# SDC-rev2.net
KiCad netlist of a schematic drawn in Altium Designer
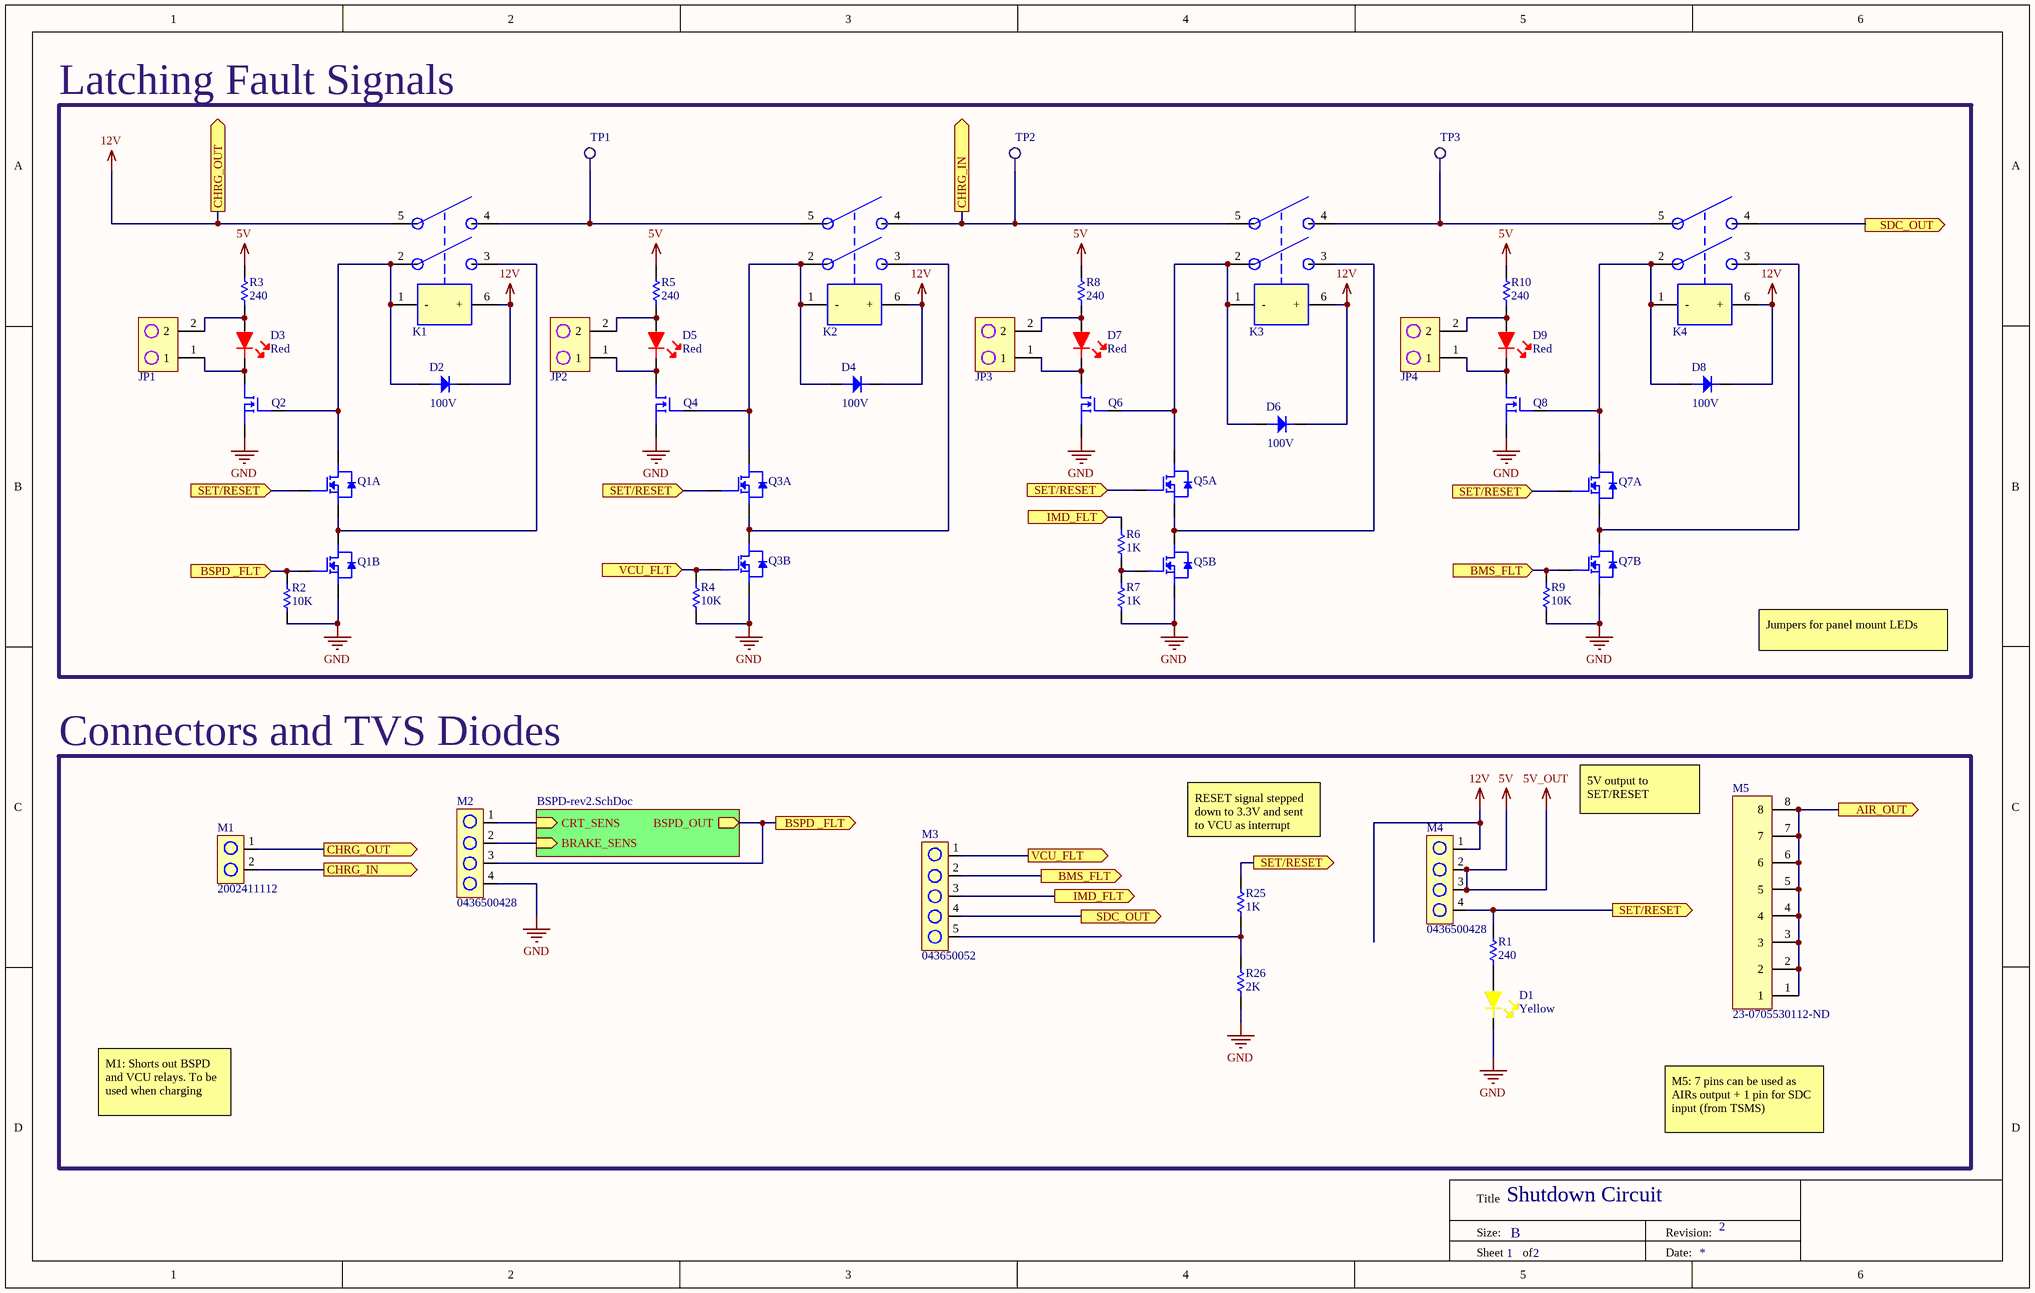
[diagram p0: SDC-rev2.SchDoc]

(export (version "E")
  (design (tool "Eeschema 10.0.6"))
  (components
    (comp (ref "D1")
      (value "Yellow")
      (footprint "LED-0603")
      (description "LED YELLOW CLEAR 0603 SMD")
      (fields
        (field (name "MANUFACTURER") "Wurth Electronics")
        (field (name "MANUFACTURER PART NUMBER") "150060YS75000")
      )
      (libsource (lib "LEDs") (part "LED-Yellow"))
    )
    (comp (ref "D2")
      (value "100V")
      (footprint "DO-214AA")
      (description "DIODE GEN PURP 600V 5A SMB")
      (fields (field (name "MANUFACTURER") "MCC") (field (name "MANUFACTURER PART NUMBER") "SK510B-LTP"))
      (libsource (lib "Diodes") (part "Diode-600V-5A"))
    )
    (comp (ref "D3")
      (value "Red")
      (footprint "LED-0603")
      (description "LED RED CLEAR 0603 SMD")
      (fields (field (name "MANUFACTURER") "Inolux") (field (name "MANUFACTURER PART NUMBER") "IN-S63ATR"))
      (libsource (lib "LEDs") (part "LED-Red-Bright"))
    )
    (comp (ref "D4")
      (value "100V")
      (footprint "DO-214AA")
      (description "DIODE GEN PURP 600V 5A SMB")
      (fields (field (name "MANUFACTURER") "MCC") (field (name "MANUFACTURER PART NUMBER") "SK510B-LTP"))
      (libsource (lib "Diodes") (part "Diode-600V-5A"))
    )
    (comp (ref "D5")
      (value "Red")
      (footprint "LED-0603")
      (description "LED RED CLEAR 0603 SMD")
      (fields (field (name "MANUFACTURER") "Inolux") (field (name "MANUFACTURER PART NUMBER") "IN-S63ATR"))
      (libsource (lib "LEDs") (part "LED-Red-Bright"))
    )
    (comp (ref "D6")
      (value "100V")
      (footprint "DO-214AA")
      (description "DIODE GEN PURP 600V 5A SMB")
      (fields (field (name "MANUFACTURER") "MCC") (field (name "MANUFACTURER PART NUMBER") "SK510B-LTP"))
      (libsource (lib "Diodes") (part "Diode-600V-5A"))
    )
    (comp (ref "D7")
      (value "Red")
      (footprint "LED-0603")
      (description "LED RED CLEAR 0603 SMD")
      (fields (field (name "MANUFACTURER") "Inolux") (field (name "MANUFACTURER PART NUMBER") "IN-S63ATR"))
      (libsource (lib "LEDs") (part "LED-Red-Bright"))
    )
    (comp (ref "D8")
      (value "100V")
      (footprint "DO-214AA")
      (description "DIODE GEN PURP 600V 5A SMB")
      (fields (field (name "MANUFACTURER") "MCC") (field (name "MANUFACTURER PART NUMBER") "SK510B-LTP"))
      (libsource (lib "Diodes") (part "Diode-600V-5A"))
    )
    (comp (ref "D9")
      (value "Red")
      (footprint "LED-0603")
      (description "LED RED CLEAR 0603 SMD")
      (fields (field (name "MANUFACTURER") "Inolux") (field (name "MANUFACTURER PART NUMBER") "IN-S63ATR"))
      (libsource (lib "LEDs") (part "LED-Red-Bright"))
    )
    (comp (ref "JP1")
      (value "732-5315-ND")
      (footprint "2PIN-JP")
      (description "CONN HEADER VERT 2POS 2.54MM")
      (libsource (lib "Connectors") (part "2PIN-TEST"))
    )
    (comp (ref "JP2")
      (value "732-5315-ND")
      (footprint "2PIN-JP")
      (description "CONN HEADER VERT 2POS 2.54MM")
      (libsource (lib "Connectors") (part "2PIN-TEST"))
    )
    (comp (ref "JP3")
      (value "732-5315-ND")
      (footprint "2PIN-JP")
      (description "CONN HEADER VERT 2POS 2.54MM")
      (libsource (lib "Connectors") (part "2PIN-TEST"))
    )
    (comp (ref "JP4")
      (value "732-5315-ND")
      (footprint "2PIN-JP")
      (description "CONN HEADER VERT 2POS 2.54MM")
      (libsource (lib "Connectors") (part "2PIN-TEST"))
    )
    (comp (ref "K1")
      (value "5-1419124-6")
      (footprint "RELAY DPST SDC")
      (description "General Purpose Relay, Osa Series, Power, Non Latching, Dpst-No, 12 Vdc, 3 A Rohs Compliant: Yes")
      (fields (field (name "MANUFACTURER") "TE Connectivity"))
      (libsource (lib "SDC") (part "5-1419124-6"))
    )
    (comp (ref "K2")
      (value "5-1419124-6")
      (footprint "RELAY DPST SDC")
      (description "General Purpose Relay, Osa Series, Power, Non Latching, Dpst-No, 12 Vdc, 3 A Rohs Compliant: Yes")
      (fields (field (name "MANUFACTURER") "TE Connectivity"))
      (libsource (lib "SDC") (part "5-1419124-6"))
    )
    (comp (ref "K3")
      (value "5-1419124-6")
      (footprint "RELAY DPST SDC")
      (description "General Purpose Relay, Osa Series, Power, Non Latching, Dpst-No, 12 Vdc, 3 A Rohs Compliant: Yes")
      (fields (field (name "MANUFACTURER") "TE Connectivity"))
      (libsource (lib "SDC") (part "5-1419124-6"))
    )
    (comp (ref "K4")
      (value "5-1419124-6")
      (footprint "RELAY DPST SDC")
      (description "General Purpose Relay, Osa Series, Power, Non Latching, Dpst-No, 12 Vdc, 3 A Rohs Compliant: Yes")
      (fields (field (name "MANUFACTURER") "TE Connectivity"))
      (libsource (lib "SDC") (part "5-1419124-6"))
    )
    (comp (ref "M1")
      (value "2002411112")
      (footprint "2-PIN MOLEX")
      (description "CONN HEADER VERT 2POS 5.7MM, 12-16AWG")
      (libsource (lib "SDC") (part "2002411112"))
    )
    (comp (ref "M2")
      (value "0436500428")
      (footprint "4-PIN MOLEX")
      (description "4 PIN HDR, 3MM PITCH, 18-30 AWG")
      (fields (field (name "MANUFACTURER") "Molex"))
      (libsource (lib "SDC") (part "0436500428"))
    )
    (comp (ref "M3")
      (value "043650052")
      (footprint "5-PIN MOLEX")
      (description "CONN HEADER VERT 5POS 3MM")
      (libsource (lib "SDC") (part "0436500528"))
    )
    (comp (ref "M4")
      (value "0436500428")
      (footprint "4-PIN MOLEX")
      (description "4 PIN HDR, 3MM PITCH, 18-30 AWG")
      (fields (field (name "MANUFACTURER") "Molex"))
      (libsource (lib "SDC") (part "0436500428"))
    )
    (comp (ref "M5")
      (value "23-0705530112-ND")
      (footprint "8PIN")
      (description "CONN HEADER R/A 8POS 2.54MM")
      (fields (field (name "MANUFACTURER") "Molex") (field (name "MANUFACTURER PART NUMBER") "70553-0112"))
      (libsource (lib "Connectors") (part "8PIN"))
    )
    (comp (ref "Q1")
      (value "DMN63D1LDW")
      (footprint "DMN63D1LDW")
      (description "MOSFET 2N-CH 60V 0.25A SOT363")
      (fields
        (field (name "MANUFACTURER") "Toshiba")
        (field (name "MANUFACTURER PART NUMBER") "SSM6N7002CFU,LF")
      )
      (libsource (lib "SDC") (part "DMN63D1LDW"))
    )
    (comp (ref "Q2")
      (value "DMN6140L-13DICT-ND")
      (footprint "SOT-23-3")
      (description "MOSFET N-CH 60V 1.6A SOT23")
      (fields (field (name "MANUFACTURER") "Diodes") (field (name "MANUFACTURER PART NUMBER") "DMN6140L-13"))
      (libsource (lib "Transistors") (part "N-FET-60V-1.6A"))
    )
    (comp (ref "Q3")
      (value "DMN63D1LDW")
      (footprint "DMN63D1LDW")
      (description "MOSFET 2N-CH 60V 0.25A SOT363")
      (fields
        (field (name "MANUFACTURER") "Toshiba")
        (field (name "MANUFACTURER PART NUMBER") "SSM6N7002CFU,LF")
      )
      (libsource (lib "SDC") (part "DMN63D1LDW"))
    )
    (comp (ref "Q4")
      (value "DMN6140L-13DICT-ND")
      (footprint "SOT-23-3")
      (description "MOSFET N-CH 60V 1.6A SOT23")
      (fields (field (name "MANUFACTURER") "Diodes") (field (name "MANUFACTURER PART NUMBER") "DMN6140L-13"))
      (libsource (lib "Transistors") (part "N-FET-60V-1.6A"))
    )
    (comp (ref "Q5")
      (value "DMN63D1LDW")
      (footprint "DMN63D1LDW")
      (description "MOSFET 2N-CH 60V 0.25A SOT363")
      (fields
        (field (name "MANUFACTURER") "Toshiba")
        (field (name "MANUFACTURER PART NUMBER") "SSM6N7002CFU,LF")
      )
      (libsource (lib "SDC") (part "DMN63D1LDW"))
    )
    (comp (ref "Q6")
      (value "DMN6140L-13DICT-ND")
      (footprint "SOT-23-3")
      (description "MOSFET N-CH 60V 1.6A SOT23")
      (fields (field (name "MANUFACTURER") "Diodes") (field (name "MANUFACTURER PART NUMBER") "DMN6140L-13"))
      (libsource (lib "Transistors") (part "N-FET-60V-1.6A"))
    )
    (comp (ref "Q7")
      (value "DMN63D1LDW")
      (footprint "DMN63D1LDW")
      (description "MOSFET 2N-CH 60V 0.25A SOT363")
      (fields
        (field (name "MANUFACTURER") "Toshiba")
        (field (name "MANUFACTURER PART NUMBER") "SSM6N7002CFU,LF")
      )
      (libsource (lib "SDC") (part "DMN63D1LDW"))
    )
    (comp (ref "Q8")
      (value "DMN6140L-13DICT-ND")
      (footprint "SOT-23-3")
      (description "MOSFET N-CH 60V 1.6A SOT23")
      (fields (field (name "MANUFACTURER") "Diodes") (field (name "MANUFACTURER PART NUMBER") "DMN6140L-13"))
      (libsource (lib "Transistors") (part "N-FET-60V-1.6A"))
    )
    (comp (ref "R1")
      (value "240")
      (footprint "RES-0603")
      (description "RES SMD 240 OHM 5% 1/4W 0603")
      (fields
        (field (name "MANUFACTURER") "Vishay")
        (field (name "MANUFACTURER PART NUMBER") "CRCW0603220RJNEA")
      )
      (libsource (lib "SDC") (part "ESR03EZPJ241"))
    )
    (comp (ref "R2")
      (value "10K")
      (footprint "RES-0603")
      (description "RES SMD 10K OHM 1% 1/10W 0603")
      (fields
        (field (name "MANUFACTURER") "Vishay")
        (field (name "MANUFACTURER PART NUMBER") "CRCW060310K0FKEA")
      )
      (libsource (lib "SDC") (part "CRCW060310K0FKEA"))
    )
    (comp (ref "R3")
      (value "240")
      (footprint "RES-0603")
      (description "RES SMD 240 OHM 5% 1/4W 0603")
      (fields
        (field (name "MANUFACTURER") "Vishay")
        (field (name "MANUFACTURER PART NUMBER") "CRCW0603220RJNEA")
      )
      (libsource (lib "SDC") (part "ESR03EZPJ241"))
    )
    (comp (ref "R4")
      (value "10K")
      (footprint "RES-0603")
      (description "RES SMD 10K OHM 1% 1/10W 0603")
      (fields
        (field (name "MANUFACTURER") "Vishay")
        (field (name "MANUFACTURER PART NUMBER") "CRCW060310K0FKEA")
      )
      (libsource (lib "SDC") (part "CRCW060310K0FKEA"))
    )
    (comp (ref "R5")
      (value "240")
      (footprint "RES-0603")
      (description "RES SMD 240 OHM 5% 1/4W 0603")
      (fields
        (field (name "MANUFACTURER") "Vishay")
        (field (name "MANUFACTURER PART NUMBER") "CRCW0603220RJNEA")
      )
      (libsource (lib "SDC") (part "ESR03EZPJ241"))
    )
    (comp (ref "R6")
      (value "1K")
      (footprint "RES-0603")
      (description "RES SMD 1K OHM 1% 1/10W 0603")
      (fields
        (field (name "MANUFACTURER") "Vishay Dale")
        (field (name "MANUFACTURER PART NUMBER") "CRCW06031K00FKEA")
      )
      (libsource (lib "SDC") (part "CRCW06031K00FKEA"))
    )
    (comp (ref "R7")
      (value "1K")
      (footprint "RES-0603")
      (description "RES SMD 1K OHM 1% 1/10W 0603")
      (fields
        (field (name "MANUFACTURER") "Vishay Dale")
        (field (name "MANUFACTURER PART NUMBER") "CRCW06031K00FKEA")
      )
      (libsource (lib "SDC") (part "CRCW06031K00FKEA"))
    )
    (comp (ref "R8")
      (value "240")
      (footprint "RES-0603")
      (description "RES SMD 240 OHM 5% 1/4W 0603")
      (fields
        (field (name "MANUFACTURER") "Vishay")
        (field (name "MANUFACTURER PART NUMBER") "CRCW0603220RJNEA")
      )
      (libsource (lib "SDC") (part "ESR03EZPJ241"))
    )
    (comp (ref "R9")
      (value "10K")
      (footprint "RES-0603")
      (description "RES SMD 10K OHM 1% 1/10W 0603")
      (fields
        (field (name "MANUFACTURER") "Vishay")
        (field (name "MANUFACTURER PART NUMBER") "CRCW060310K0FKEA")
      )
      (libsource (lib "SDC") (part "CRCW060310K0FKEA"))
    )
    (comp (ref "R10")
      (value "240")
      (footprint "RES-0603")
      (description "RES SMD 240 OHM 5% 1/4W 0603")
      (fields
        (field (name "MANUFACTURER") "Vishay")
        (field (name "MANUFACTURER PART NUMBER") "CRCW0603220RJNEA")
      )
      (libsource (lib "SDC") (part "ESR03EZPJ241"))
    )
    (comp (ref "R25")
      (value "1K")
      (footprint "RES-0603")
      (description "RES SMD 240 OHM 5% 1/4W 0603")
      (fields
        (field (name "MANUFACTURER") "Vishay")
        (field (name "MANUFACTURER PART NUMBER") "CRCW0603220RJNEA")
      )
      (libsource (lib "SDC") (part "ESR03EZPJ241"))
    )
    (comp (ref "R26")
      (value "2K")
      (footprint "RES-0603")
      (description "RES SMD 2K OHM 0.1% 1/10W 0603")
      (fields
        (field (name "MANUFACTURER") "Vishay Dale")
        (field (name "MANUFACTURER PART NUMBER") "CRCW06031K00FKEA")
      )
      (libsource (lib "SDC") (part "ERA-3AEB202V"))
    )
    (comp (ref "TP1")
      (value "Testpoint2")
      (footprint "TP2")
      (description "Single layer pad TP")
      (libsource (lib "Misc") (part "Testpoint2"))
    )
    (comp (ref "TP2")
      (value "Testpoint2")
      (footprint "TP2")
      (description "Single layer pad TP")
      (libsource (lib "Misc") (part "Testpoint2"))
    )
    (comp (ref "TP3")
      (value "Testpoint2")
      (footprint "TP2")
      (description "Single layer pad TP")
      (libsource (lib "Misc") (part "Testpoint2"))
    )
  )
  (nets
    (net (code "1") (name "/AIR_OUT") (class "Default")
      (node (ref "M5") (pin "1") (pinfunction "1_1") (pintype "passive"))
      (node (ref "M5") (pin "2") (pinfunction "2_2") (pintype "passive"))
      (node (ref "M5") (pin "3") (pinfunction "3_3") (pintype "passive"))
      (node (ref "M5") (pin "4") (pinfunction "4_4") (pintype "passive"))
      (node (ref "M5") (pin "5") (pinfunction "5_5") (pintype "passive"))
      (node (ref "M5") (pin "6") (pinfunction "6_6") (pintype "passive"))
      (node (ref "M5") (pin "7") (pinfunction "7_7") (pintype "passive"))
      (node (ref "M5") (pin "8") (pinfunction "8_8") (pintype "passive"))
    )
    (net (code "2") (name "/BMS_FLT") (class "Default")
      (node (ref "M3") (pin "2") (pinfunction "2_2") (pintype "passive"))
      (node (ref "Q7") (pin "5") (pinfunction "G2_5") (pintype "passive"))
      (node (ref "R9") (pin "1") (pinfunction "1_1") (pintype "passive"))
    )
    (net (code "3") (name "/BRAKE_SENS") (class "Default")
      (node (ref "M2") (pin "2") (pinfunction "2_2") (pintype "passive"))
    )
    (net (code "4") (name "/BSPD _FLT") (class "Default")
      (node (ref "M2") (pin "3") (pinfunction "3_3") (pintype "passive"))
      (node (ref "Q1") (pin "5") (pinfunction "G2_5") (pintype "passive"))
      (node (ref "R2") (pin "1") (pinfunction "1_1") (pintype "passive"))
    )
    (net (code "5") (name "/CHRG_IN") (class "Default")
      (node (ref "K2") (pin "4") (pintype "passive"))
      (node (ref "K3") (pin "5") (pintype "passive"))
      (node (ref "M1") (pin "2") (pinfunction "2_2") (pintype "passive"))
      (node (ref "TP2") (pin "1") (pinfunction "1_1") (pintype "passive"))
    )
    (net (code "6") (name "/CRT_SENS") (class "Default")
      (node (ref "M2") (pin "1") (pinfunction "1_1") (pintype "passive"))
    )
    (net (code "7") (name "/IMD_FLT") (class "Default")
      (node (ref "M3") (pin "3") (pinfunction "3_3") (pintype "passive"))
      (node (ref "R6") (pin "1") (pinfunction "1_1") (pintype "passive"))
    )
    (net (code "8") (name "/SDC_OUT") (class "Default")
      (node (ref "K4") (pin "4") (pintype "passive"))
      (node (ref "M3") (pin "4") (pinfunction "4_4") (pintype "passive"))
    )
    (net (code "9") (name "/SET{slash}RESET") (class "Default")
      (node (ref "M4") (pin "4") (pinfunction "4_4") (pintype "passive"))
      (node (ref "Q1") (pin "2") (pinfunction "G1_2") (pintype "passive"))
      (node (ref "Q3") (pin "2") (pinfunction "G1_2") (pintype "passive"))
      (node (ref "Q5") (pin "2") (pinfunction "G1_2") (pintype "passive"))
      (node (ref "Q7") (pin "2") (pinfunction "G1_2") (pintype "passive"))
      (node (ref "R1") (pin "2") (pinfunction "2_2") (pintype "passive"))
      (node (ref "R25") (pin "2") (pinfunction "2_2") (pintype "passive"))
    )
    (net (code "10") (name "/VCU_FLT") (class "Default")
      (node (ref "M3") (pin "1") (pinfunction "1_1") (pintype "passive"))
      (node (ref "Q3") (pin "5") (pinfunction "G2_5") (pintype "passive"))
      (node (ref "R4") (pin "1") (pinfunction "1_1") (pintype "passive"))
    )
    (net (code "11") (name "5V") (class "Default")
      (node (ref "M4") (pin "2") (pinfunction "2_2") (pintype "passive"))
      (node (ref "M4") (pin "3") (pinfunction "3_3") (pintype "passive"))
      (node (ref "R10") (pin "2") (pinfunction "2_2") (pintype "passive"))
      (node (ref "R3") (pin "2") (pinfunction "2_2") (pintype "passive"))
      (node (ref "R5") (pin "2") (pinfunction "2_2") (pintype "passive"))
      (node (ref "R8") (pin "2") (pinfunction "2_2") (pintype "passive"))
    )
    (net (code "12") (name "12V") (class "Default")
      (node (ref "D2") (pin "1") (pinfunction "1_1") (pintype "passive"))
      (node (ref "D4") (pin "1") (pinfunction "1_1") (pintype "passive"))
      (node (ref "D6") (pin "1") (pinfunction "1_1") (pintype "passive"))
      (node (ref "D8") (pin "1") (pinfunction "1_1") (pintype "passive"))
      (node (ref "K1") (pin "5") (pintype "passive"))
      (node (ref "K1") (pin "6") (pinfunction "+_6") (pintype "passive"))
      (node (ref "K2") (pin "6") (pinfunction "+_6") (pintype "passive"))
      (node (ref "K3") (pin "6") (pinfunction "+_6") (pintype "passive"))
      (node (ref "K4") (pin "6") (pinfunction "+_6") (pintype "passive"))
      (node (ref "M1") (pin "1") (pinfunction "1_1") (pintype "passive"))
      (node (ref "M4") (pin "1") (pinfunction "1_1") (pintype "passive"))
    )
    (net (code "13") (name "GND") (class "Default")
      (node (ref "D1") (pin "2") (pinfunction "2_2") (pintype "passive"))
      (node (ref "M2") (pin "4") (pinfunction "4_4") (pintype "passive"))
      (node (ref "Q1") (pin "4") (pinfunction "S2_4") (pintype "passive"))
      (node (ref "Q2") (pin "3") (pinfunction "3_3") (pintype "passive"))
      (node (ref "Q3") (pin "4") (pinfunction "S2_4") (pintype "passive"))
      (node (ref "Q4") (pin "3") (pinfunction "3_3") (pintype "passive"))
      (node (ref "Q5") (pin "4") (pinfunction "S2_4") (pintype "passive"))
      (node (ref "Q6") (pin "3") (pinfunction "3_3") (pintype "passive"))
      (node (ref "Q7") (pin "4") (pinfunction "S2_4") (pintype "passive"))
      (node (ref "Q8") (pin "3") (pinfunction "3_3") (pintype "passive"))
      (node (ref "R2") (pin "2") (pinfunction "2_2") (pintype "passive"))
      (node (ref "R26") (pin "1") (pinfunction "1_1") (pintype "passive"))
      (node (ref "R4") (pin "2") (pinfunction "2_2") (pintype "passive"))
      (node (ref "R7") (pin "2") (pinfunction "2_2") (pintype "passive"))
      (node (ref "R9") (pin "2") (pinfunction "2_2") (pintype "passive"))
    )
    (net (code "14") (name "Net-(D1-Pad1)") (class "Default")
      (node (ref "D1") (pin "1") (pinfunction "1_1") (pintype "passive"))
      (node (ref "R1") (pin "1") (pinfunction "1_1") (pintype "passive"))
    )
    (net (code "15") (name "Net-(D3-Pad1)") (class "Default")
      (node (ref "D3") (pin "1") (pinfunction "1_1") (pintype "passive"))
      (node (ref "JP1") (pin "2") (pinfunction "2_2") (pintype "passive"))
      (node (ref "R3") (pin "1") (pinfunction "1_1") (pintype "passive"))
    )
    (net (code "16") (name "Net-(D3-Pad2)") (class "Default")
      (node (ref "D3") (pin "2") (pinfunction "2_2") (pintype "passive"))
      (node (ref "JP1") (pin "1") (pinfunction "1_1") (pintype "passive"))
      (node (ref "Q2") (pin "2") (pinfunction "2_2") (pintype "passive"))
    )
    (net (code "17") (name "Net-(D5-Pad1)") (class "Default")
      (node (ref "D5") (pin "1") (pinfunction "1_1") (pintype "passive"))
      (node (ref "JP2") (pin "2") (pinfunction "2_2") (pintype "passive"))
      (node (ref "R5") (pin "1") (pinfunction "1_1") (pintype "passive"))
    )
    (net (code "18") (name "Net-(D5-Pad2)") (class "Default")
      (node (ref "D5") (pin "2") (pinfunction "2_2") (pintype "passive"))
      (node (ref "JP2") (pin "1") (pinfunction "1_1") (pintype "passive"))
      (node (ref "Q4") (pin "2") (pinfunction "2_2") (pintype "passive"))
    )
    (net (code "19") (name "Net-(D7-Pad1)") (class "Default")
      (node (ref "D7") (pin "1") (pinfunction "1_1") (pintype "passive"))
      (node (ref "JP3") (pin "2") (pinfunction "2_2") (pintype "passive"))
      (node (ref "R8") (pin "1") (pinfunction "1_1") (pintype "passive"))
    )
    (net (code "20") (name "Net-(D7-Pad2)") (class "Default")
      (node (ref "D7") (pin "2") (pinfunction "2_2") (pintype "passive"))
      (node (ref "JP3") (pin "1") (pinfunction "1_1") (pintype "passive"))
      (node (ref "Q6") (pin "2") (pinfunction "2_2") (pintype "passive"))
    )
    (net (code "21") (name "Net-(D9-Pad1)") (class "Default")
      (node (ref "D9") (pin "1") (pinfunction "1_1") (pintype "passive"))
      (node (ref "JP4") (pin "2") (pinfunction "2_2") (pintype "passive"))
      (node (ref "R10") (pin "1") (pinfunction "1_1") (pintype "passive"))
    )
    (net (code "22") (name "Net-(D9-Pad2)") (class "Default")
      (node (ref "D9") (pin "2") (pinfunction "2_2") (pintype "passive"))
      (node (ref "JP4") (pin "1") (pinfunction "1_1") (pintype "passive"))
      (node (ref "Q8") (pin "2") (pinfunction "2_2") (pintype "passive"))
    )
    (net (code "23") (name "Net-(K1--)") (class "Default")
      (node (ref "D2") (pin "2") (pinfunction "2_2") (pintype "passive"))
      (node (ref "K1") (pin "1") (pinfunction "-_1") (pintype "passive"))
      (node (ref "K1") (pin "2") (pintype "passive"))
      (node (ref "Q1") (pin "6") (pinfunction "D1_6") (pintype "passive"))
      (node (ref "Q2") (pin "1") (pinfunction "1_1") (pintype "passive"))
    )
    (net (code "24") (name "Net-(K1-Pad4)") (class "Default")
      (node (ref "K1") (pin "4") (pintype "passive"))
      (node (ref "K2") (pin "5") (pintype "passive"))
      (node (ref "TP1") (pin "1") (pinfunction "1_1") (pintype "passive"))
    )
    (net (code "25") (name "Net-(K2--)") (class "Default")
      (node (ref "D4") (pin "2") (pinfunction "2_2") (pintype "passive"))
      (node (ref "K2") (pin "1") (pinfunction "-_1") (pintype "passive"))
      (node (ref "K2") (pin "2") (pintype "passive"))
      (node (ref "Q3") (pin "6") (pinfunction "D1_6") (pintype "passive"))
      (node (ref "Q4") (pin "1") (pinfunction "1_1") (pintype "passive"))
    )
    (net (code "26") (name "Net-(K3--)") (class "Default")
      (node (ref "D6") (pin "2") (pinfunction "2_2") (pintype "passive"))
      (node (ref "K3") (pin "1") (pinfunction "-_1") (pintype "passive"))
      (node (ref "K3") (pin "2") (pintype "passive"))
      (node (ref "Q5") (pin "6") (pinfunction "D1_6") (pintype "passive"))
      (node (ref "Q6") (pin "1") (pinfunction "1_1") (pintype "passive"))
    )
    (net (code "27") (name "Net-(K3-Pad4)") (class "Default")
      (node (ref "K3") (pin "4") (pintype "passive"))
      (node (ref "K4") (pin "5") (pintype "passive"))
      (node (ref "TP3") (pin "1") (pinfunction "1_1") (pintype "passive"))
    )
    (net (code "28") (name "Net-(K4--)") (class "Default")
      (node (ref "D8") (pin "2") (pinfunction "2_2") (pintype "passive"))
      (node (ref "K4") (pin "1") (pinfunction "-_1") (pintype "passive"))
      (node (ref "K4") (pin "2") (pintype "passive"))
      (node (ref "Q7") (pin "6") (pinfunction "D1_6") (pintype "passive"))
      (node (ref "Q8") (pin "1") (pinfunction "1_1") (pintype "passive"))
    )
    (net (code "29") (name "Net-(M3-Pad5)") (class "Default")
      (node (ref "M3") (pin "5") (pinfunction "5_5") (pintype "passive"))
      (node (ref "R25") (pin "1") (pinfunction "1_1") (pintype "passive"))
      (node (ref "R26") (pin "2") (pinfunction "2_2") (pintype "passive"))
    )
    (net (code "30") (name "Net-(Q1A-S1)") (class "Default")
      (node (ref "K1") (pin "3") (pintype "passive"))
      (node (ref "Q1") (pin "1") (pinfunction "S1_1") (pintype "passive"))
      (node (ref "Q1") (pin "3") (pinfunction "D2_3") (pintype "passive"))
    )
    (net (code "31") (name "Net-(Q3A-S1)") (class "Default")
      (node (ref "K2") (pin "3") (pintype "passive"))
      (node (ref "Q3") (pin "1") (pinfunction "S1_1") (pintype "passive"))
      (node (ref "Q3") (pin "3") (pinfunction "D2_3") (pintype "passive"))
    )
    (net (code "32") (name "Net-(Q5A-S1)") (class "Default")
      (node (ref "K3") (pin "3") (pintype "passive"))
      (node (ref "Q5") (pin "1") (pinfunction "S1_1") (pintype "passive"))
      (node (ref "Q5") (pin "3") (pinfunction "D2_3") (pintype "passive"))
    )
    (net (code "33") (name "Net-(Q5B-G2)") (class "Default")
      (node (ref "Q5") (pin "5") (pinfunction "G2_5") (pintype "passive"))
      (node (ref "R6") (pin "2") (pinfunction "2_2") (pintype "passive"))
      (node (ref "R7") (pin "1") (pinfunction "1_1") (pintype "passive"))
    )
    (net (code "34") (name "Net-(Q7A-S1)") (class "Default")
      (node (ref "K4") (pin "3") (pintype "passive"))
      (node (ref "Q7") (pin "1") (pinfunction "S1_1") (pintype "passive"))
      (node (ref "Q7") (pin "3") (pinfunction "D2_3") (pintype "passive"))
    )
  )
)
